# AMU-S25-V00-DAUGHTERIMDConnection.net
KiCad netlist of a schematic drawn in Altium Designer
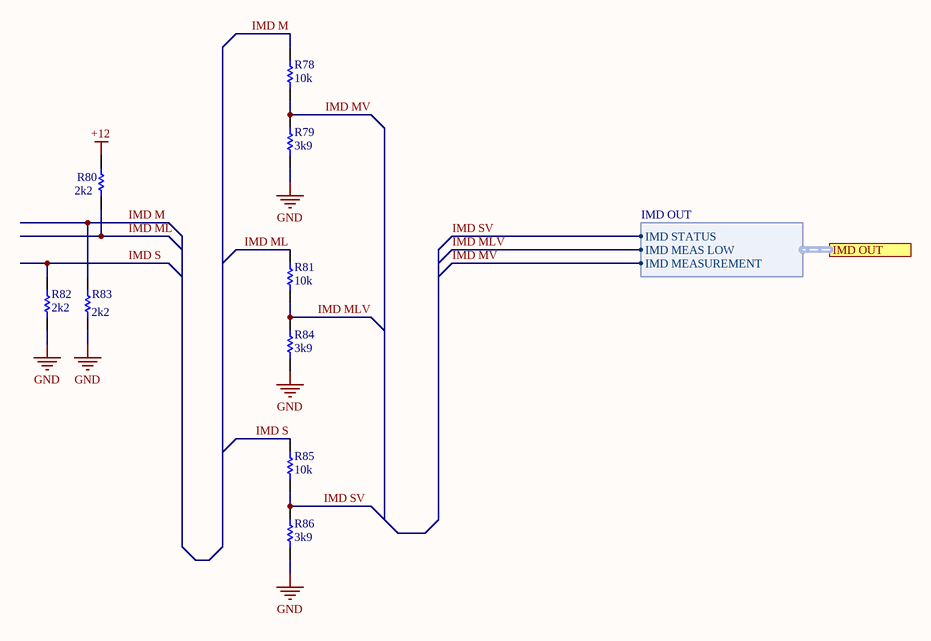
[diagram p0: AMU-S25-V00-DAUGHTERIMDConnection.SchDoc]

(export (version "E")
  (design (tool "Eeschema 10.0.6"))
  (components
    (comp (ref "R78")
      (value "10k")
      (footprint "Res_ThinFilm_0603")
      (description "Resistor, SMD, 10k, 0.1W, 1%, 0603")
      (libsource (lib "StandardResistors") (part "10k 1% 0603"))
    )
    (comp (ref "R79")
      (value "3k9")
      (footprint "Res_ThinFilm_0603")
      (description "Resistor, SMD, 3k9, 0.1W, 5%, 0603")
      (libsource (lib "StandardResistors") (part "3k9 5% 0603"))
    )
    (comp (ref "R80")
      (value "2k2")
      (footprint "Res_ThinFilm_0603")
      (description "Resistor, SMD, 2k2, 0.1W, 5%, 0603")
      (libsource (lib "StandardResistors") (part "2k2 5% 0603"))
    )
    (comp (ref "R81")
      (value "10k")
      (footprint "Res_ThinFilm_0603")
      (description "Resistor, SMD, 10k, 0.1W, 1%, 0603")
      (libsource (lib "StandardResistors") (part "10k 1% 0603"))
    )
    (comp (ref "R82")
      (value "2k2")
      (footprint "Res_ThinFilm_0603")
      (description "Resistor, SMD, 2k2, 0.1W, 5%, 0603")
      (libsource (lib "StandardResistors") (part "2k2 5% 0603"))
    )
    (comp (ref "R83")
      (value "2k2")
      (footprint "Res_ThinFilm_0603")
      (description "Resistor, SMD, 2k2, 0.1W, 5%, 0603")
      (libsource (lib "StandardResistors") (part "2k2 5% 0603"))
    )
    (comp (ref "R84")
      (value "3k9")
      (footprint "Res_ThinFilm_0603")
      (description "Resistor, SMD, 3k9, 0.1W, 5%, 0603")
      (libsource (lib "StandardResistors") (part "3k9 5% 0603"))
    )
    (comp (ref "R85")
      (value "10k")
      (footprint "Res_ThinFilm_0603")
      (description "Resistor, SMD, 10k, 0.1W, 1%, 0603")
      (libsource (lib "StandardResistors") (part "10k 1% 0603"))
    )
    (comp (ref "R86")
      (value "3k9")
      (footprint "Res_ThinFilm_0603")
      (description "Resistor, SMD, 3k9, 0.1W, 5%, 0603")
      (libsource (lib "StandardResistors") (part "3k9 5% 0603"))
    )
  )
  (nets
    (net (code "3") (name "+12") (class "Default")
      (node (ref "R80") (pin "2") (pinfunction "2_2") (pintype "passive"))
    )
    (net (code "4") (name "/IMD M") (class "Default")
      (node (ref "R78") (pin "2") (pinfunction "2_2") (pintype "passive"))
      (node (ref "R83") (pin "2") (pinfunction "2_2") (pintype "passive"))
    )
    (net (code "5") (name "/IMD ML") (class "Default")
      (node (ref "R80") (pin "1") (pinfunction "1_1") (pintype "passive"))
      (node (ref "R81") (pin "2") (pinfunction "2_2") (pintype "passive"))
    )
    (net (code "6") (name "/IMD MLV") (class "Default")
      (node (ref "R81") (pin "1") (pinfunction "1_1") (pintype "passive"))
      (node (ref "R84") (pin "2") (pinfunction "2_2") (pintype "passive"))
    )
    (net (code "7") (name "/IMD MV") (class "Default")
      (node (ref "R78") (pin "1") (pinfunction "1_1") (pintype "passive"))
      (node (ref "R79") (pin "2") (pinfunction "2_2") (pintype "passive"))
    )
    (net (code "8") (name "/IMD S") (class "Default")
      (node (ref "R82") (pin "2") (pinfunction "2_2") (pintype "passive"))
      (node (ref "R85") (pin "2") (pinfunction "2_2") (pintype "passive"))
    )
    (net (code "9") (name "/IMD SV") (class "Default")
      (node (ref "R85") (pin "1") (pinfunction "1_1") (pintype "passive"))
      (node (ref "R86") (pin "2") (pinfunction "2_2") (pintype "passive"))
    )
    (net (code "11") (name "GND") (class "Default")
      (node (ref "R79") (pin "1") (pinfunction "1_1") (pintype "passive"))
      (node (ref "R82") (pin "1") (pinfunction "1_1") (pintype "passive"))
      (node (ref "R83") (pin "1") (pinfunction "1_1") (pintype "passive"))
      (node (ref "R84") (pin "1") (pinfunction "1_1") (pintype "passive"))
      (node (ref "R86") (pin "1") (pinfunction "1_1") (pintype "passive"))
    )
  )
)
